# BitAccumulator.net
KiCad netlist of a schematic drawn in EAGLE
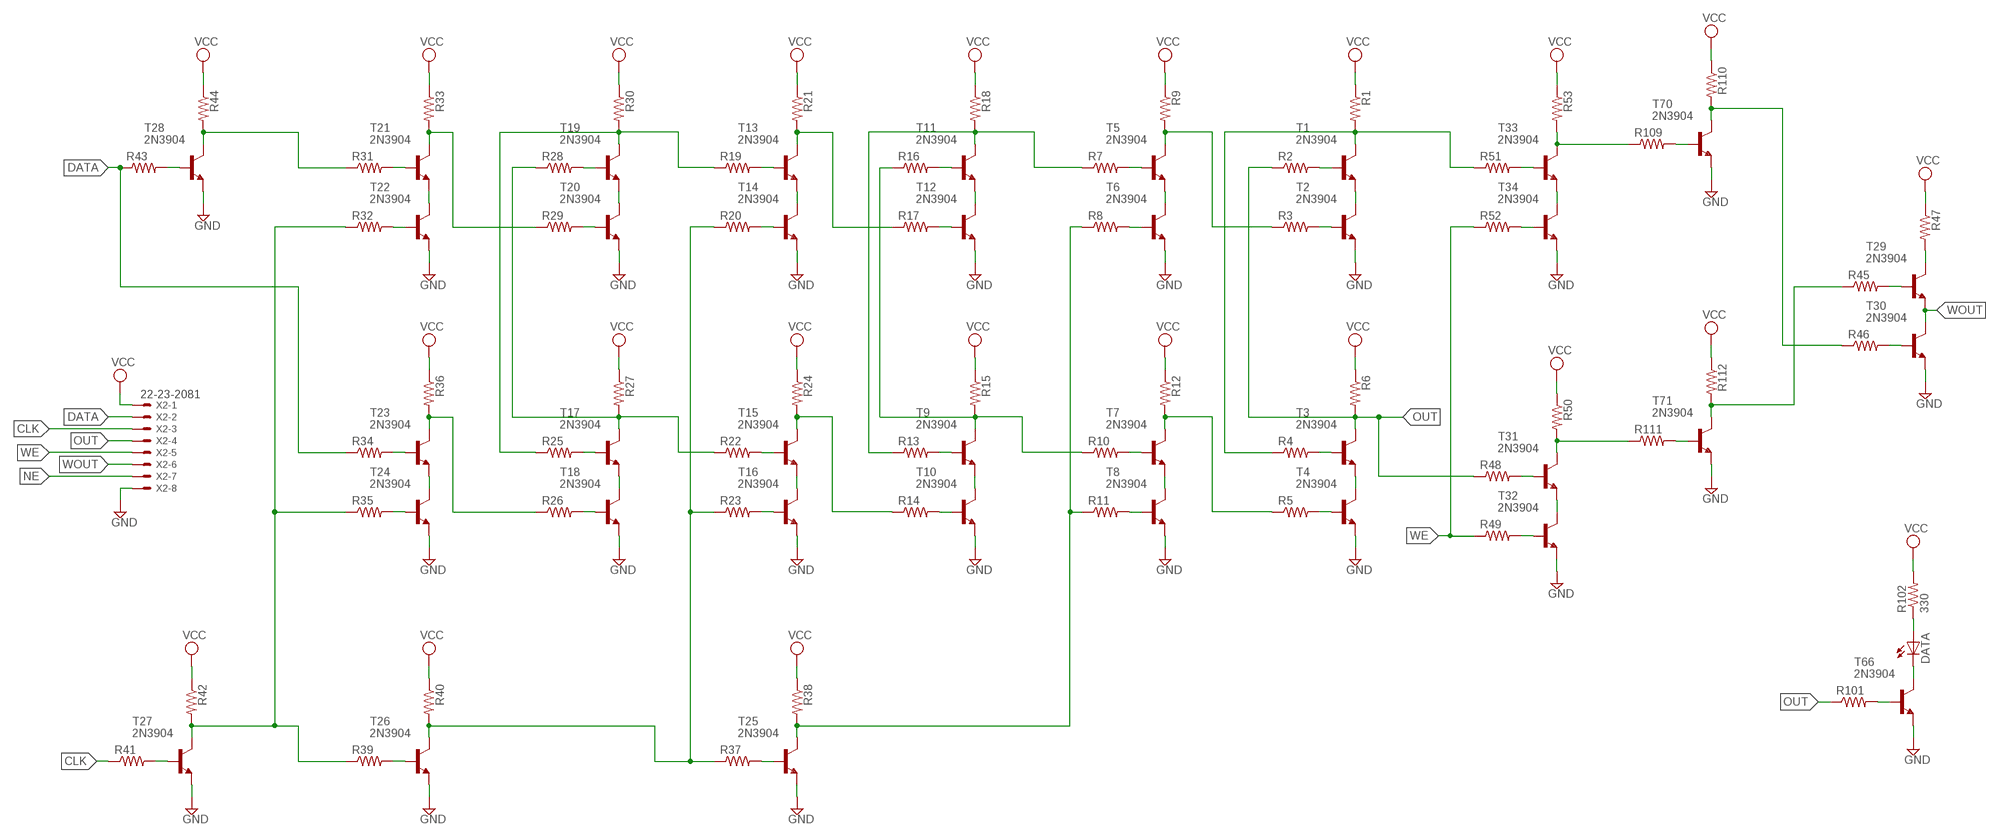
[diagram p0: schematic, sheet 1]

(export (version "E")
  (design (tool "Eeschema 10.0.6"))
  (components
    (comp (ref "DATA")
      (value "LED5MM")
      (footprint "eagle-import:LED5MM")
      (libsource (lib "eagle-import") (part "LED5MM"))
    )
    (comp (ref "R1")
      (value "R-US_0309/10")
      (footprint "eagle-import:0309_10")
      (libsource (lib "eagle-import") (part "R-US_0309/10"))
    )
    (comp (ref "R2")
      (value "R-US_0309/10")
      (footprint "eagle-import:0309_10")
      (libsource (lib "eagle-import") (part "R-US_0309/10"))
    )
    (comp (ref "R3")
      (value "R-US_0309/10")
      (footprint "eagle-import:0309_10")
      (libsource (lib "eagle-import") (part "R-US_0309/10"))
    )
    (comp (ref "R4")
      (value "R-US_0309/10")
      (footprint "eagle-import:0309_10")
      (libsource (lib "eagle-import") (part "R-US_0309/10"))
    )
    (comp (ref "R5")
      (value "R-US_0309/10")
      (footprint "eagle-import:0309_10")
      (libsource (lib "eagle-import") (part "R-US_0309/10"))
    )
    (comp (ref "R6")
      (value "R-US_0309/10")
      (footprint "eagle-import:0309_10")
      (libsource (lib "eagle-import") (part "R-US_0309/10"))
    )
    (comp (ref "R7")
      (value "R-US_0309/10")
      (footprint "eagle-import:0309_10")
      (libsource (lib "eagle-import") (part "R-US_0309/10"))
    )
    (comp (ref "R8")
      (value "R-US_0309/10")
      (footprint "eagle-import:0309_10")
      (libsource (lib "eagle-import") (part "R-US_0309/10"))
    )
    (comp (ref "R9")
      (value "R-US_0309/10")
      (footprint "eagle-import:0309_10")
      (libsource (lib "eagle-import") (part "R-US_0309/10"))
    )
    (comp (ref "R10")
      (value "R-US_0309/10")
      (footprint "eagle-import:0309_10")
      (libsource (lib "eagle-import") (part "R-US_0309/10"))
    )
    (comp (ref "R11")
      (value "R-US_0309/10")
      (footprint "eagle-import:0309_10")
      (libsource (lib "eagle-import") (part "R-US_0309/10"))
    )
    (comp (ref "R12")
      (value "R-US_0309/10")
      (footprint "eagle-import:0309_10")
      (libsource (lib "eagle-import") (part "R-US_0309/10"))
    )
    (comp (ref "R13")
      (value "R-US_0309/10")
      (footprint "eagle-import:0309_10")
      (libsource (lib "eagle-import") (part "R-US_0309/10"))
    )
    (comp (ref "R14")
      (value "R-US_0309/10")
      (footprint "eagle-import:0309_10")
      (libsource (lib "eagle-import") (part "R-US_0309/10"))
    )
    (comp (ref "R15")
      (value "R-US_0309/10")
      (footprint "eagle-import:0309_10")
      (libsource (lib "eagle-import") (part "R-US_0309/10"))
    )
    (comp (ref "R16")
      (value "R-US_0309/10")
      (footprint "eagle-import:0309_10")
      (libsource (lib "eagle-import") (part "R-US_0309/10"))
    )
    (comp (ref "R17")
      (value "R-US_0309/10")
      (footprint "eagle-import:0309_10")
      (libsource (lib "eagle-import") (part "R-US_0309/10"))
    )
    (comp (ref "R18")
      (value "R-US_0309/10")
      (footprint "eagle-import:0309_10")
      (libsource (lib "eagle-import") (part "R-US_0309/10"))
    )
    (comp (ref "R19")
      (value "R-US_0309/10")
      (footprint "eagle-import:0309_10")
      (libsource (lib "eagle-import") (part "R-US_0309/10"))
    )
    (comp (ref "R20")
      (value "R-US_0309/10")
      (footprint "eagle-import:0309_10")
      (libsource (lib "eagle-import") (part "R-US_0309/10"))
    )
    (comp (ref "R21")
      (value "R-US_0309/10")
      (footprint "eagle-import:0309_10")
      (libsource (lib "eagle-import") (part "R-US_0309/10"))
    )
    (comp (ref "R22")
      (value "R-US_0309/10")
      (footprint "eagle-import:0309_10")
      (libsource (lib "eagle-import") (part "R-US_0309/10"))
    )
    (comp (ref "R23")
      (value "R-US_0309/10")
      (footprint "eagle-import:0309_10")
      (libsource (lib "eagle-import") (part "R-US_0309/10"))
    )
    (comp (ref "R24")
      (value "R-US_0309/10")
      (footprint "eagle-import:0309_10")
      (libsource (lib "eagle-import") (part "R-US_0309/10"))
    )
    (comp (ref "R25")
      (value "R-US_0309/10")
      (footprint "eagle-import:0309_10")
      (libsource (lib "eagle-import") (part "R-US_0309/10"))
    )
    (comp (ref "R26")
      (value "R-US_0309/10")
      (footprint "eagle-import:0309_10")
      (libsource (lib "eagle-import") (part "R-US_0309/10"))
    )
    (comp (ref "R27")
      (value "R-US_0309/10")
      (footprint "eagle-import:0309_10")
      (libsource (lib "eagle-import") (part "R-US_0309/10"))
    )
    (comp (ref "R28")
      (value "R-US_0309/10")
      (footprint "eagle-import:0309_10")
      (libsource (lib "eagle-import") (part "R-US_0309/10"))
    )
    (comp (ref "R29")
      (value "R-US_0309/10")
      (footprint "eagle-import:0309_10")
      (libsource (lib "eagle-import") (part "R-US_0309/10"))
    )
    (comp (ref "R30")
      (value "R-US_0309/10")
      (footprint "eagle-import:0309_10")
      (libsource (lib "eagle-import") (part "R-US_0309/10"))
    )
    (comp (ref "R31")
      (value "R-US_0309/10")
      (footprint "eagle-import:0309_10")
      (libsource (lib "eagle-import") (part "R-US_0309/10"))
    )
    (comp (ref "R32")
      (value "R-US_0309/10")
      (footprint "eagle-import:0309_10")
      (libsource (lib "eagle-import") (part "R-US_0309/10"))
    )
    (comp (ref "R33")
      (value "R-US_0309/10")
      (footprint "eagle-import:0309_10")
      (libsource (lib "eagle-import") (part "R-US_0309/10"))
    )
    (comp (ref "R34")
      (value "R-US_0309/10")
      (footprint "eagle-import:0309_10")
      (libsource (lib "eagle-import") (part "R-US_0309/10"))
    )
    (comp (ref "R35")
      (value "R-US_0309/10")
      (footprint "eagle-import:0309_10")
      (libsource (lib "eagle-import") (part "R-US_0309/10"))
    )
    (comp (ref "R36")
      (value "R-US_0309/10")
      (footprint "eagle-import:0309_10")
      (libsource (lib "eagle-import") (part "R-US_0309/10"))
    )
    (comp (ref "R37")
      (value "R-US_0309/10")
      (footprint "eagle-import:0309_10")
      (libsource (lib "eagle-import") (part "R-US_0309/10"))
    )
    (comp (ref "R38")
      (value "R-US_0309/10")
      (footprint "eagle-import:0309_10")
      (libsource (lib "eagle-import") (part "R-US_0309/10"))
    )
    (comp (ref "R39")
      (value "R-US_0309/10")
      (footprint "eagle-import:0309_10")
      (libsource (lib "eagle-import") (part "R-US_0309/10"))
    )
    (comp (ref "R40")
      (value "R-US_0309/10")
      (footprint "eagle-import:0309_10")
      (libsource (lib "eagle-import") (part "R-US_0309/10"))
    )
    (comp (ref "R41")
      (value "R-US_0309/10")
      (footprint "eagle-import:0309_10")
      (libsource (lib "eagle-import") (part "R-US_0309/10"))
    )
    (comp (ref "R42")
      (value "R-US_0309/10")
      (footprint "eagle-import:0309_10")
      (libsource (lib "eagle-import") (part "R-US_0309/10"))
    )
    (comp (ref "R43")
      (value "R-US_0309/10")
      (footprint "eagle-import:0309_10")
      (libsource (lib "eagle-import") (part "R-US_0309/10"))
    )
    (comp (ref "R44")
      (value "R-US_0309/10")
      (footprint "eagle-import:0309_10")
      (libsource (lib "eagle-import") (part "R-US_0309/10"))
    )
    (comp (ref "R45")
      (value "R-US_0309/10")
      (footprint "eagle-import:0309_10")
      (libsource (lib "eagle-import") (part "R-US_0309/10"))
    )
    (comp (ref "R46")
      (value "R-US_0309/10")
      (footprint "eagle-import:0309_10")
      (libsource (lib "eagle-import") (part "R-US_0309/10"))
    )
    (comp (ref "R47")
      (value "R-US_0309/10")
      (footprint "eagle-import:0309_10")
      (libsource (lib "eagle-import") (part "R-US_0309/10"))
    )
    (comp (ref "R48")
      (value "R-US_0309/10")
      (footprint "eagle-import:0309_10")
      (libsource (lib "eagle-import") (part "R-US_0309/10"))
    )
    (comp (ref "R49")
      (value "R-US_0309/10")
      (footprint "eagle-import:0309_10")
      (libsource (lib "eagle-import") (part "R-US_0309/10"))
    )
    (comp (ref "R50")
      (value "R-US_0309/10")
      (footprint "eagle-import:0309_10")
      (libsource (lib "eagle-import") (part "R-US_0309/10"))
    )
    (comp (ref "R51")
      (value "R-US_0309/10")
      (footprint "eagle-import:0309_10")
      (libsource (lib "eagle-import") (part "R-US_0309/10"))
    )
    (comp (ref "R52")
      (value "R-US_0309/10")
      (footprint "eagle-import:0309_10")
      (libsource (lib "eagle-import") (part "R-US_0309/10"))
    )
    (comp (ref "R53")
      (value "R-US_0309/10")
      (footprint "eagle-import:0309_10")
      (libsource (lib "eagle-import") (part "R-US_0309/10"))
    )
    (comp (ref "R101")
      (value "R-US_0309/10")
      (footprint "eagle-import:0309_10")
      (libsource (lib "eagle-import") (part "R-US_0309/10"))
    )
    (comp (ref "R102")
      (value "330")
      (footprint "eagle-import:0309_10")
      (libsource (lib "eagle-import") (part "R-US_0309/10"))
    )
    (comp (ref "R109")
      (value "R-US_0309/10")
      (footprint "eagle-import:0309_10")
      (libsource (lib "eagle-import") (part "R-US_0309/10"))
    )
    (comp (ref "R110")
      (value "R-US_0309/10")
      (footprint "eagle-import:0309_10")
      (libsource (lib "eagle-import") (part "R-US_0309/10"))
    )
    (comp (ref "R111")
      (value "R-US_0309/10")
      (footprint "eagle-import:0309_10")
      (libsource (lib "eagle-import") (part "R-US_0309/10"))
    )
    (comp (ref "R112")
      (value "R-US_0309/10")
      (footprint "eagle-import:0309_10")
      (libsource (lib "eagle-import") (part "R-US_0309/10"))
    )
    (comp (ref "T1")
      (value "2N3904")
      (footprint "eagle-import:TO92")
      (libsource (lib "eagle-import") (part "2N3904"))
    )
    (comp (ref "T2")
      (value "2N3904")
      (footprint "eagle-import:TO92")
      (libsource (lib "eagle-import") (part "2N3904"))
    )
    (comp (ref "T3")
      (value "2N3904")
      (footprint "eagle-import:TO92")
      (libsource (lib "eagle-import") (part "2N3904"))
    )
    (comp (ref "T4")
      (value "2N3904")
      (footprint "eagle-import:TO92")
      (libsource (lib "eagle-import") (part "2N3904"))
    )
    (comp (ref "T5")
      (value "2N3904")
      (footprint "eagle-import:TO92")
      (libsource (lib "eagle-import") (part "2N3904"))
    )
    (comp (ref "T6")
      (value "2N3904")
      (footprint "eagle-import:TO92")
      (libsource (lib "eagle-import") (part "2N3904"))
    )
    (comp (ref "T7")
      (value "2N3904")
      (footprint "eagle-import:TO92")
      (libsource (lib "eagle-import") (part "2N3904"))
    )
    (comp (ref "T8")
      (value "2N3904")
      (footprint "eagle-import:TO92")
      (libsource (lib "eagle-import") (part "2N3904"))
    )
    (comp (ref "T9")
      (value "2N3904")
      (footprint "eagle-import:TO92")
      (libsource (lib "eagle-import") (part "2N3904"))
    )
    (comp (ref "T10")
      (value "2N3904")
      (footprint "eagle-import:TO92")
      (libsource (lib "eagle-import") (part "2N3904"))
    )
    (comp (ref "T11")
      (value "2N3904")
      (footprint "eagle-import:TO92")
      (libsource (lib "eagle-import") (part "2N3904"))
    )
    (comp (ref "T12")
      (value "2N3904")
      (footprint "eagle-import:TO92")
      (libsource (lib "eagle-import") (part "2N3904"))
    )
    (comp (ref "T13")
      (value "2N3904")
      (footprint "eagle-import:TO92")
      (libsource (lib "eagle-import") (part "2N3904"))
    )
    (comp (ref "T14")
      (value "2N3904")
      (footprint "eagle-import:TO92")
      (libsource (lib "eagle-import") (part "2N3904"))
    )
    (comp (ref "T15")
      (value "2N3904")
      (footprint "eagle-import:TO92")
      (libsource (lib "eagle-import") (part "2N3904"))
    )
    (comp (ref "T16")
      (value "2N3904")
      (footprint "eagle-import:TO92")
      (libsource (lib "eagle-import") (part "2N3904"))
    )
    (comp (ref "T17")
      (value "2N3904")
      (footprint "eagle-import:TO92")
      (libsource (lib "eagle-import") (part "2N3904"))
    )
    (comp (ref "T18")
      (value "2N3904")
      (footprint "eagle-import:TO92")
      (libsource (lib "eagle-import") (part "2N3904"))
    )
    (comp (ref "T19")
      (value "2N3904")
      (footprint "eagle-import:TO92")
      (libsource (lib "eagle-import") (part "2N3904"))
    )
    (comp (ref "T20")
      (value "2N3904")
      (footprint "eagle-import:TO92")
      (libsource (lib "eagle-import") (part "2N3904"))
    )
    (comp (ref "T21")
      (value "2N3904")
      (footprint "eagle-import:TO92")
      (libsource (lib "eagle-import") (part "2N3904"))
    )
    (comp (ref "T22")
      (value "2N3904")
      (footprint "eagle-import:TO92")
      (libsource (lib "eagle-import") (part "2N3904"))
    )
    (comp (ref "T23")
      (value "2N3904")
      (footprint "eagle-import:TO92")
      (libsource (lib "eagle-import") (part "2N3904"))
    )
    (comp (ref "T24")
      (value "2N3904")
      (footprint "eagle-import:TO92")
      (libsource (lib "eagle-import") (part "2N3904"))
    )
    (comp (ref "T25")
      (value "2N3904")
      (footprint "eagle-import:TO92")
      (libsource (lib "eagle-import") (part "2N3904"))
    )
    (comp (ref "T26")
      (value "2N3904")
      (footprint "eagle-import:TO92")
      (libsource (lib "eagle-import") (part "2N3904"))
    )
    (comp (ref "T27")
      (value "2N3904")
      (footprint "eagle-import:TO92")
      (libsource (lib "eagle-import") (part "2N3904"))
    )
    (comp (ref "T28")
      (value "2N3904")
      (footprint "eagle-import:TO92")
      (libsource (lib "eagle-import") (part "2N3904"))
    )
    (comp (ref "T29")
      (value "2N3904")
      (footprint "eagle-import:TO92")
      (libsource (lib "eagle-import") (part "2N3904"))
    )
    (comp (ref "T30")
      (value "2N3904")
      (footprint "eagle-import:TO92")
      (libsource (lib "eagle-import") (part "2N3904"))
    )
    (comp (ref "T31")
      (value "2N3904")
      (footprint "eagle-import:TO92")
      (libsource (lib "eagle-import") (part "2N3904"))
    )
    (comp (ref "T32")
      (value "2N3904")
      (footprint "eagle-import:TO92")
      (libsource (lib "eagle-import") (part "2N3904"))
    )
    (comp (ref "T33")
      (value "2N3904")
      (footprint "eagle-import:TO92")
      (libsource (lib "eagle-import") (part "2N3904"))
    )
    (comp (ref "T34")
      (value "2N3904")
      (footprint "eagle-import:TO92")
      (libsource (lib "eagle-import") (part "2N3904"))
    )
    (comp (ref "T66")
      (value "2N3904")
      (footprint "eagle-import:TO92")
      (libsource (lib "eagle-import") (part "2N3904"))
    )
    (comp (ref "T70")
      (value "2N3904")
      (footprint "eagle-import:TO92")
      (libsource (lib "eagle-import") (part "2N3904"))
    )
    (comp (ref "T71")
      (value "2N3904")
      (footprint "eagle-import:TO92")
      (libsource (lib "eagle-import") (part "2N3904"))
    )
    (comp (ref "X2")
      (value "22-23-2081")
      (footprint "eagle-import:22-23-2081")
      (fields (field (name "MF") "MOLEX"))
      (libsource (lib "eagle-import") (part "22-23-2081"))
    )
  )
  (nets
    (net (code "1") (name "CLK") (class "Default")
      (node (ref "R41") (pin "1") (pinfunction "1_1") (pintype "passive"))
      (node (ref "X2") (pin "3") (pinfunction "S_3") (pintype "passive"))
    )
    (net (code "2") (name "DATA") (class "Default")
      (node (ref "R34") (pin "1") (pinfunction "1_1") (pintype "passive"))
      (node (ref "R43") (pin "1") (pinfunction "1_1") (pintype "passive"))
      (node (ref "X2") (pin "2") (pinfunction "S_2") (pintype "passive"))
    )
    (net (code "3") (name "GND") (class "Default")
      (node (ref "T10") (pin "3") (pinfunction "E_3") (pintype "passive"))
      (node (ref "T12") (pin "3") (pinfunction "E_3") (pintype "passive"))
      (node (ref "T14") (pin "3") (pinfunction "E_3") (pintype "passive"))
      (node (ref "T16") (pin "3") (pinfunction "E_3") (pintype "passive"))
      (node (ref "T18") (pin "3") (pinfunction "E_3") (pintype "passive"))
      (node (ref "T2") (pin "3") (pinfunction "E_3") (pintype "passive"))
      (node (ref "T20") (pin "3") (pinfunction "E_3") (pintype "passive"))
      (node (ref "T22") (pin "3") (pinfunction "E_3") (pintype "passive"))
      (node (ref "T24") (pin "3") (pinfunction "E_3") (pintype "passive"))
      (node (ref "T25") (pin "3") (pinfunction "E_3") (pintype "passive"))
      (node (ref "T26") (pin "3") (pinfunction "E_3") (pintype "passive"))
      (node (ref "T27") (pin "3") (pinfunction "E_3") (pintype "passive"))
      (node (ref "T28") (pin "3") (pinfunction "E_3") (pintype "passive"))
      (node (ref "T30") (pin "3") (pinfunction "E_3") (pintype "passive"))
      (node (ref "T32") (pin "3") (pinfunction "E_3") (pintype "passive"))
      (node (ref "T34") (pin "3") (pinfunction "E_3") (pintype "passive"))
      (node (ref "T4") (pin "3") (pinfunction "E_3") (pintype "passive"))
      (node (ref "T6") (pin "3") (pinfunction "E_3") (pintype "passive"))
      (node (ref "T66") (pin "3") (pinfunction "E_3") (pintype "passive"))
      (node (ref "T70") (pin "3") (pinfunction "E_3") (pintype "passive"))
      (node (ref "T71") (pin "3") (pinfunction "E_3") (pintype "passive"))
      (node (ref "T8") (pin "3") (pinfunction "E_3") (pintype "passive"))
      (node (ref "X2") (pin "8") (pinfunction "S_8") (pintype "passive"))
    )
    (net (code "4") (name "NE") (class "Default")
      (node (ref "X2") (pin "7") (pinfunction "S_7") (pintype "passive"))
    )
    (net (code "5") (name "Net-(DATA-C)") (class "Default")
      (node (ref "DATA") (pin "K") (pinfunction "C_K") (pintype "passive"))
      (node (ref "T66") (pin "1") (pinfunction "C_1") (pintype "passive"))
    )
    (net (code "6") (name "Net-(DATA-PadA)") (class "Default")
      (node (ref "DATA") (pin "A") (pinfunction "A_A") (pintype "passive"))
      (node (ref "R102") (pin "1") (pinfunction "1_1") (pintype "passive"))
    )
    (net (code "7") (name "Net-(T1-B)") (class "Default")
      (node (ref "R2") (pin "2") (pinfunction "2_2") (pintype "passive"))
      (node (ref "T1") (pin "2") (pinfunction "B_2") (pintype "passive"))
    )
    (net (code "8") (name "Net-(T1-C)") (class "Default")
      (node (ref "R1") (pin "2") (pinfunction "2_2") (pintype "passive"))
      (node (ref "R4") (pin "1") (pinfunction "1_1") (pintype "passive"))
      (node (ref "R51") (pin "1") (pinfunction "1_1") (pintype "passive"))
      (node (ref "T1") (pin "1") (pinfunction "C_1") (pintype "passive"))
    )
    (net (code "9") (name "Net-(T1-E)") (class "Default")
      (node (ref "T1") (pin "3") (pinfunction "E_3") (pintype "passive"))
      (node (ref "T2") (pin "1") (pinfunction "C_1") (pintype "passive"))
    )
    (net (code "10") (name "Net-(T2-B)") (class "Default")
      (node (ref "R3") (pin "2") (pinfunction "2_2") (pintype "passive"))
      (node (ref "T2") (pin "2") (pinfunction "B_2") (pintype "passive"))
    )
    (net (code "11") (name "Net-(T3-B)") (class "Default")
      (node (ref "R4") (pin "2") (pinfunction "2_2") (pintype "passive"))
      (node (ref "T3") (pin "2") (pinfunction "B_2") (pintype "passive"))
    )
    (net (code "12") (name "Net-(T3-E)") (class "Default")
      (node (ref "T3") (pin "3") (pinfunction "E_3") (pintype "passive"))
      (node (ref "T4") (pin "1") (pinfunction "C_1") (pintype "passive"))
    )
    (net (code "13") (name "Net-(T4-B)") (class "Default")
      (node (ref "R5") (pin "2") (pinfunction "2_2") (pintype "passive"))
      (node (ref "T4") (pin "2") (pinfunction "B_2") (pintype "passive"))
    )
    (net (code "14") (name "Net-(T5-B)") (class "Default")
      (node (ref "R7") (pin "2") (pinfunction "2_2") (pintype "passive"))
      (node (ref "T5") (pin "2") (pinfunction "B_2") (pintype "passive"))
    )
    (net (code "15") (name "Net-(T5-C)") (class "Default")
      (node (ref "R3") (pin "1") (pinfunction "1_1") (pintype "passive"))
      (node (ref "R9") (pin "2") (pinfunction "2_2") (pintype "passive"))
      (node (ref "T5") (pin "1") (pinfunction "C_1") (pintype "passive"))
    )
    (net (code "16") (name "Net-(T5-E)") (class "Default")
      (node (ref "T5") (pin "3") (pinfunction "E_3") (pintype "passive"))
      (node (ref "T6") (pin "1") (pinfunction "C_1") (pintype "passive"))
    )
    (net (code "17") (name "Net-(T6-B)") (class "Default")
      (node (ref "R8") (pin "2") (pinfunction "2_2") (pintype "passive"))
      (node (ref "T6") (pin "2") (pinfunction "B_2") (pintype "passive"))
    )
    (net (code "18") (name "Net-(T7-B)") (class "Default")
      (node (ref "R10") (pin "2") (pinfunction "2_2") (pintype "passive"))
      (node (ref "T7") (pin "2") (pinfunction "B_2") (pintype "passive"))
    )
    (net (code "19") (name "Net-(T7-C)") (class "Default")
      (node (ref "R12") (pin "2") (pinfunction "2_2") (pintype "passive"))
      (node (ref "R5") (pin "1") (pinfunction "1_1") (pintype "passive"))
      (node (ref "T7") (pin "1") (pinfunction "C_1") (pintype "passive"))
    )
    (net (code "20") (name "Net-(T7-E)") (class "Default")
      (node (ref "T7") (pin "3") (pinfunction "E_3") (pintype "passive"))
      (node (ref "T8") (pin "1") (pinfunction "C_1") (pintype "passive"))
    )
    (net (code "21") (name "Net-(T8-B)") (class "Default")
      (node (ref "R11") (pin "2") (pinfunction "2_2") (pintype "passive"))
      (node (ref "T8") (pin "2") (pinfunction "B_2") (pintype "passive"))
    )
    (net (code "22") (name "Net-(T9-B)") (class "Default")
      (node (ref "R13") (pin "2") (pinfunction "2_2") (pintype "passive"))
      (node (ref "T9") (pin "2") (pinfunction "B_2") (pintype "passive"))
    )
    (net (code "23") (name "Net-(T9-C)") (class "Default")
      (node (ref "R10") (pin "1") (pinfunction "1_1") (pintype "passive"))
      (node (ref "R15") (pin "2") (pinfunction "2_2") (pintype "passive"))
      (node (ref "R16") (pin "1") (pinfunction "1_1") (pintype "passive"))
      (node (ref "T9") (pin "1") (pinfunction "C_1") (pintype "passive"))
    )
    (net (code "24") (name "Net-(T10-B)") (class "Default")
      (node (ref "R14") (pin "2") (pinfunction "2_2") (pintype "passive"))
      (node (ref "T10") (pin "2") (pinfunction "B_2") (pintype "passive"))
    )
    (net (code "25") (name "Net-(T10-C)") (class "Default")
      (node (ref "T10") (pin "1") (pinfunction "C_1") (pintype "passive"))
      (node (ref "T9") (pin "3") (pinfunction "E_3") (pintype "passive"))
    )
    (net (code "26") (name "Net-(T11-B)") (class "Default")
      (node (ref "R16") (pin "2") (pinfunction "2_2") (pintype "passive"))
      (node (ref "T11") (pin "2") (pinfunction "B_2") (pintype "passive"))
    )
    (net (code "27") (name "Net-(T11-C)") (class "Default")
      (node (ref "R13") (pin "1") (pinfunction "1_1") (pintype "passive"))
      (node (ref "R18") (pin "2") (pinfunction "2_2") (pintype "passive"))
      (node (ref "R7") (pin "1") (pinfunction "1_1") (pintype "passive"))
      (node (ref "T11") (pin "1") (pinfunction "C_1") (pintype "passive"))
    )
    (net (code "28") (name "Net-(T11-E)") (class "Default")
      (node (ref "T11") (pin "3") (pinfunction "E_3") (pintype "passive"))
      (node (ref "T12") (pin "1") (pinfunction "C_1") (pintype "passive"))
    )
    (net (code "29") (name "Net-(T12-B)") (class "Default")
      (node (ref "R17") (pin "2") (pinfunction "2_2") (pintype "passive"))
      (node (ref "T12") (pin "2") (pinfunction "B_2") (pintype "passive"))
    )
    (net (code "30") (name "Net-(T13-B)") (class "Default")
      (node (ref "R19") (pin "2") (pinfunction "2_2") (pintype "passive"))
      (node (ref "T13") (pin "2") (pinfunction "B_2") (pintype "passive"))
    )
    (net (code "31") (name "Net-(T13-C)") (class "Default")
      (node (ref "R17") (pin "1") (pinfunction "1_1") (pintype "passive"))
      (node (ref "R21") (pin "2") (pinfunction "2_2") (pintype "passive"))
      (node (ref "T13") (pin "1") (pinfunction "C_1") (pintype "passive"))
    )
    (net (code "32") (name "Net-(T13-E)") (class "Default")
      (node (ref "T13") (pin "3") (pinfunction "E_3") (pintype "passive"))
      (node (ref "T14") (pin "1") (pinfunction "C_1") (pintype "passive"))
    )
    (net (code "33") (name "Net-(T14-B)") (class "Default")
      (node (ref "R20") (pin "2") (pinfunction "2_2") (pintype "passive"))
      (node (ref "T14") (pin "2") (pinfunction "B_2") (pintype "passive"))
    )
    (net (code "34") (name "Net-(T15-B)") (class "Default")
      (node (ref "R22") (pin "2") (pinfunction "2_2") (pintype "passive"))
      (node (ref "T15") (pin "2") (pinfunction "B_2") (pintype "passive"))
    )
    (net (code "35") (name "Net-(T15-C)") (class "Default")
      (node (ref "R14") (pin "1") (pinfunction "1_1") (pintype "passive"))
      (node (ref "R24") (pin "2") (pinfunction "2_2") (pintype "passive"))
      (node (ref "T15") (pin "1") (pinfunction "C_1") (pintype "passive"))
    )
    (net (code "36") (name "Net-(T15-E)") (class "Default")
      (node (ref "T15") (pin "3") (pinfunction "E_3") (pintype "passive"))
      (node (ref "T16") (pin "1") (pinfunction "C_1") (pintype "passive"))
    )
    (net (code "37") (name "Net-(T16-B)") (class "Default")
      (node (ref "R23") (pin "2") (pinfunction "2_2") (pintype "passive"))
      (node (ref "T16") (pin "2") (pinfunction "B_2") (pintype "passive"))
    )
    (net (code "38") (name "Net-(T17-B)") (class "Default")
      (node (ref "R25") (pin "2") (pinfunction "2_2") (pintype "passive"))
      (node (ref "T17") (pin "2") (pinfunction "B_2") (pintype "passive"))
    )
    (net (code "39") (name "Net-(T17-C)") (class "Default")
      (node (ref "R22") (pin "1") (pinfunction "1_1") (pintype "passive"))
      (node (ref "R27") (pin "2") (pinfunction "2_2") (pintype "passive"))
      (node (ref "R28") (pin "1") (pinfunction "1_1") (pintype "passive"))
      (node (ref "T17") (pin "1") (pinfunction "C_1") (pintype "passive"))
    )
    (net (code "40") (name "Net-(T17-E)") (class "Default")
      (node (ref "T17") (pin "3") (pinfunction "E_3") (pintype "passive"))
      (node (ref "T18") (pin "1") (pinfunction "C_1") (pintype "passive"))
    )
    (net (code "41") (name "Net-(T18-B)") (class "Default")
      (node (ref "R26") (pin "2") (pinfunction "2_2") (pintype "passive"))
      (node (ref "T18") (pin "2") (pinfunction "B_2") (pintype "passive"))
    )
    (net (code "42") (name "Net-(T19-B)") (class "Default")
      (node (ref "R28") (pin "2") (pinfunction "2_2") (pintype "passive"))
      (node (ref "T19") (pin "2") (pinfunction "B_2") (pintype "passive"))
    )
    (net (code "43") (name "Net-(T19-C)") (class "Default")
      (node (ref "R19") (pin "1") (pinfunction "1_1") (pintype "passive"))
      (node (ref "R25") (pin "1") (pinfunction "1_1") (pintype "passive"))
      (node (ref "R30") (pin "2") (pinfunction "2_2") (pintype "passive"))
      (node (ref "T19") (pin "1") (pinfunction "C_1") (pintype "passive"))
    )
    (net (code "44") (name "Net-(T19-E)") (class "Default")
      (node (ref "T19") (pin "3") (pinfunction "E_3") (pintype "passive"))
      (node (ref "T20") (pin "1") (pinfunction "C_1") (pintype "passive"))
    )
    (net (code "45") (name "Net-(T20-B)") (class "Default")
      (node (ref "R29") (pin "2") (pinfunction "2_2") (pintype "passive"))
      (node (ref "T20") (pin "2") (pinfunction "B_2") (pintype "passive"))
    )
    (net (code "46") (name "Net-(T21-B)") (class "Default")
      (node (ref "R31") (pin "2") (pinfunction "2_2") (pintype "passive"))
      (node (ref "T21") (pin "2") (pinfunction "B_2") (pintype "passive"))
    )
    (net (code "47") (name "Net-(T21-C)") (class "Default")
      (node (ref "R29") (pin "1") (pinfunction "1_1") (pintype "passive"))
      (node (ref "R33") (pin "2") (pinfunction "2_2") (pintype "passive"))
      (node (ref "T21") (pin "1") (pinfunction "C_1") (pintype "passive"))
    )
    (net (code "48") (name "Net-(T21-E)") (class "Default")
      (node (ref "T21") (pin "3") (pinfunction "E_3") (pintype "passive"))
      (node (ref "T22") (pin "1") (pinfunction "C_1") (pintype "passive"))
    )
    (net (code "49") (name "Net-(T22-B)") (class "Default")
      (node (ref "R32") (pin "2") (pinfunction "2_2") (pintype "passive"))
      (node (ref "T22") (pin "2") (pinfunction "B_2") (pintype "passive"))
    )
    (net (code "50") (name "Net-(T23-B)") (class "Default")
      (node (ref "R34") (pin "2") (pinfunction "2_2") (pintype "passive"))
      (node (ref "T23") (pin "2") (pinfunction "B_2") (pintype "passive"))
    )
    (net (code "51") (name "Net-(T23-C)") (class "Default")
      (node (ref "R26") (pin "1") (pinfunction "1_1") (pintype "passive"))
      (node (ref "R36") (pin "2") (pinfunction "2_2") (pintype "passive"))
      (node (ref "T23") (pin "1") (pinfunction "C_1") (pintype "passive"))
    )
    (net (code "52") (name "Net-(T23-E)") (class "Default")
      (node (ref "T23") (pin "3") (pinfunction "E_3") (pintype "passive"))
      (node (ref "T24") (pin "1") (pinfunction "C_1") (pintype "passive"))
    )
    (net (code "53") (name "Net-(T24-B)") (class "Default")
      (node (ref "R35") (pin "2") (pinfunction "2_2") (pintype "passive"))
      (node (ref "T24") (pin "2") (pinfunction "B_2") (pintype "passive"))
    )
    (net (code "54") (name "Net-(T25-B)") (class "Default")
      (node (ref "R37") (pin "2") (pinfunction "2_2") (pintype "passive"))
      (node (ref "T25") (pin "2") (pinfunction "B_2") (pintype "passive"))
    )
    (net (code "55") (name "Net-(T25-C)") (class "Default")
      (node (ref "R11") (pin "1") (pinfunction "1_1") (pintype "passive"))
      (node (ref "R38") (pin "2") (pinfunction "2_2") (pintype "passive"))
      (node (ref "R8") (pin "1") (pinfunction "1_1") (pintype "passive"))
      (node (ref "T25") (pin "1") (pinfunction "C_1") (pintype "passive"))
    )
    (net (code "56") (name "Net-(T26-B)") (class "Default")
      (node (ref "R39") (pin "2") (pinfunction "2_2") (pintype "passive"))
      (node (ref "T26") (pin "2") (pinfunction "B_2") (pintype "passive"))
    )
    (net (code "57") (name "Net-(T26-C)") (class "Default")
      (node (ref "R20") (pin "1") (pinfunction "1_1") (pintype "passive"))
      (node (ref "R23") (pin "1") (pinfunction "1_1") (pintype "passive"))
      (node (ref "R37") (pin "1") (pinfunction "1_1") (pintype "passive"))
      (node (ref "R40") (pin "2") (pinfunction "2_2") (pintype "passive"))
      (node (ref "T26") (pin "1") (pinfunction "C_1") (pintype "passive"))
    )
    (net (code "58") (name "Net-(T27-B)") (class "Default")
      (node (ref "R41") (pin "2") (pinfunction "2_2") (pintype "passive"))
      (node (ref "T27") (pin "2") (pinfunction "B_2") (pintype "passive"))
    )
    (net (code "59") (name "Net-(T27-C)") (class "Default")
      (node (ref "R32") (pin "1") (pinfunction "1_1") (pintype "passive"))
      (node (ref "R35") (pin "1") (pinfunction "1_1") (pintype "passive"))
      (node (ref "R39") (pin "1") (pinfunction "1_1") (pintype "passive"))
      (node (ref "R42") (pin "2") (pinfunction "2_2") (pintype "passive"))
      (node (ref "T27") (pin "1") (pinfunction "C_1") (pintype "passive"))
    )
    (net (code "60") (name "Net-(T28-B)") (class "Default")
      (node (ref "R43") (pin "2") (pinfunction "2_2") (pintype "passive"))
      (node (ref "T28") (pin "2") (pinfunction "B_2") (pintype "passive"))
    )
    (net (code "61") (name "Net-(T28-C)") (class "Default")
      (node (ref "R31") (pin "1") (pinfunction "1_1") (pintype "passive"))
      (node (ref "R44") (pin "2") (pinfunction "2_2") (pintype "passive"))
      (node (ref "T28") (pin "1") (pinfunction "C_1") (pintype "passive"))
    )
    (net (code "62") (name "Net-(T29-B)") (class "Default")
      (node (ref "R45") (pin "2") (pinfunction "2_2") (pintype "passive"))
      (node (ref "T29") (pin "2") (pinfunction "B_2") (pintype "passive"))
    )
    (net (code "63") (name "Net-(T29-C)") (class "Default")
      (node (ref "R47") (pin "2") (pinfunction "2_2") (pintype "passive"))
      (node (ref "T29") (pin "1") (pinfunction "C_1") (pintype "passive"))
    )
    (net (code "64") (name "Net-(T30-B)") (class "Default")
      (node (ref "R46") (pin "2") (pinfunction "2_2") (pintype "passive"))
      (node (ref "T30") (pin "2") (pinfunction "B_2") (pintype "passive"))
    )
    (net (code "65") (name "Net-(T31-B)") (class "Default")
      (node (ref "R48") (pin "2") (pinfunction "2_2") (pintype "passive"))
      (node (ref "T31") (pin "2") (pinfunction "B_2") (pintype "passive"))
    )
    (net (code "66") (name "Net-(T31-C)") (class "Default")
      (node (ref "R111") (pin "1") (pinfunction "1_1") (pintype "passive"))
      (node (ref "R50") (pin "2") (pinfunction "2_2") (pintype "passive"))
      (node (ref "T31") (pin "1") (pinfunction "C_1") (pintype "passive"))
    )
    (net (code "67") (name "Net-(T31-E)") (class "Default")
      (node (ref "T31") (pin "3") (pinfunction "E_3") (pintype "passive"))
      (node (ref "T32") (pin "1") (pinfunction "C_1") (pintype "passive"))
    )
    (net (code "68") (name "Net-(T32-B)") (class "Default")
      (node (ref "R49") (pin "2") (pinfunction "2_2") (pintype "passive"))
      (node (ref "T32") (pin "2") (pinfunction "B_2") (pintype "passive"))
    )
    (net (code "69") (name "Net-(T33-B)") (class "Default")
      (node (ref "R51") (pin "2") (pinfunction "2_2") (pintype "passive"))
      (node (ref "T33") (pin "2") (pinfunction "B_2") (pintype "passive"))
    )
    (net (code "70") (name "Net-(T33-C)") (class "Default")
      (node (ref "R109") (pin "1") (pinfunction "1_1") (pintype "passive"))
      (node (ref "R53") (pin "2") (pinfunction "2_2") (pintype "passive"))
      (node (ref "T33") (pin "1") (pinfunction "C_1") (pintype "passive"))
    )
    (net (code "71") (name "Net-(T33-E)") (class "Default")
      (node (ref "T33") (pin "3") (pinfunction "E_3") (pintype "passive"))
      (node (ref "T34") (pin "1") (pinfunction "C_1") (pintype "passive"))
    )
    (net (code "72") (name "Net-(T34-B)") (class "Default")
      (node (ref "R52") (pin "2") (pinfunction "2_2") (pintype "passive"))
      (node (ref "T34") (pin "2") (pinfunction "B_2") (pintype "passive"))
    )
    (net (code "73") (name "Net-(T66-B)") (class "Default")
      (node (ref "R101") (pin "2") (pinfunction "2_2") (pintype "passive"))
      (node (ref "T66") (pin "2") (pinfunction "B_2") (pintype "passive"))
    )
    (net (code "74") (name "Net-(T70-B)") (class "Default")
      (node (ref "R109") (pin "2") (pinfunction "2_2") (pintype "passive"))
      (node (ref "T70") (pin "2") (pinfunction "B_2") (pintype "passive"))
    )
    (net (code "75") (name "Net-(T70-C)") (class "Default")
      (node (ref "R110") (pin "2") (pinfunction "2_2") (pintype "passive"))
      (node (ref "R46") (pin "1") (pinfunction "1_1") (pintype "passive"))
      (node (ref "T70") (pin "1") (pinfunction "C_1") (pintype "passive"))
    )
    (net (code "76") (name "Net-(T71-B)") (class "Default")
      (node (ref "R111") (pin "2") (pinfunction "2_2") (pintype "passive"))
      (node (ref "T71") (pin "2") (pinfunction "B_2") (pintype "passive"))
    )
    (net (code "77") (name "Net-(T71-C)") (class "Default")
      (node (ref "R112") (pin "2") (pinfunction "2_2") (pintype "passive"))
      (node (ref "R45") (pin "1") (pinfunction "1_1") (pintype "passive"))
      (node (ref "T71") (pin "1") (pinfunction "C_1") (pintype "passive"))
    )
    (net (code "78") (name "OUT") (class "Default")
      (node (ref "R101") (pin "1") (pinfunction "1_1") (pintype "passive"))
      (node (ref "R2") (pin "1") (pinfunction "1_1") (pintype "passive"))
      (node (ref "R48") (pin "1") (pinfunction "1_1") (pintype "passive"))
      (node (ref "R6") (pin "2") (pinfunction "2_2") (pintype "passive"))
      (node (ref "T3") (pin "1") (pinfunction "C_1") (pintype "passive"))
      (node (ref "X2") (pin "4") (pinfunction "S_4") (pintype "passive"))
    )
    (net (code "79") (name "VCC") (class "Default")
      (node (ref "R1") (pin "1") (pinfunction "1_1") (pintype "passive"))
      (node (ref "R102") (pin "2") (pinfunction "2_2") (pintype "passive"))
      (node (ref "R110") (pin "1") (pinfunction "1_1") (pintype "passive"))
      (node (ref "R112") (pin "1") (pinfunction "1_1") (pintype "passive"))
      (node (ref "R12") (pin "1") (pinfunction "1_1") (pintype "passive"))
      (node (ref "R15") (pin "1") (pinfunction "1_1") (pintype "passive"))
      (node (ref "R18") (pin "1") (pinfunction "1_1") (pintype "passive"))
      (node (ref "R21") (pin "1") (pinfunction "1_1") (pintype "passive"))
      (node (ref "R24") (pin "1") (pinfunction "1_1") (pintype "passive"))
      (node (ref "R27") (pin "1") (pinfunction "1_1") (pintype "passive"))
      (node (ref "R30") (pin "1") (pinfunction "1_1") (pintype "passive"))
      (node (ref "R33") (pin "1") (pinfunction "1_1") (pintype "passive"))
      (node (ref "R36") (pin "1") (pinfunction "1_1") (pintype "passive"))
      (node (ref "R38") (pin "1") (pinfunction "1_1") (pintype "passive"))
      (node (ref "R40") (pin "1") (pinfunction "1_1") (pintype "passive"))
      (node (ref "R42") (pin "1") (pinfunction "1_1") (pintype "passive"))
      (node (ref "R44") (pin "1") (pinfunction "1_1") (pintype "passive"))
      (node (ref "R47") (pin "1") (pinfunction "1_1") (pintype "passive"))
      (node (ref "R50") (pin "1") (pinfunction "1_1") (pintype "passive"))
      (node (ref "R53") (pin "1") (pinfunction "1_1") (pintype "passive"))
      (node (ref "R6") (pin "1") (pinfunction "1_1") (pintype "passive"))
      (node (ref "R9") (pin "1") (pinfunction "1_1") (pintype "passive"))
      (node (ref "X2") (pin "1") (pinfunction "S_1") (pintype "passive"))
    )
    (net (code "80") (name "WE") (class "Default")
      (node (ref "R49") (pin "1") (pinfunction "1_1") (pintype "passive"))
      (node (ref "R52") (pin "1") (pinfunction "1_1") (pintype "passive"))
      (node (ref "X2") (pin "5") (pinfunction "S_5") (pintype "passive"))
    )
    (net (code "81") (name "WOUT") (class "Default")
      (node (ref "T29") (pin "3") (pinfunction "E_3") (pintype "passive"))
      (node (ref "T30") (pin "1") (pinfunction "C_1") (pintype "passive"))
      (node (ref "X2") (pin "6") (pinfunction "S_6") (pintype "passive"))
    )
  )
)
